# USB2MCV_REV1.net
KiCad netlist of a schematic drawn in EAGLE
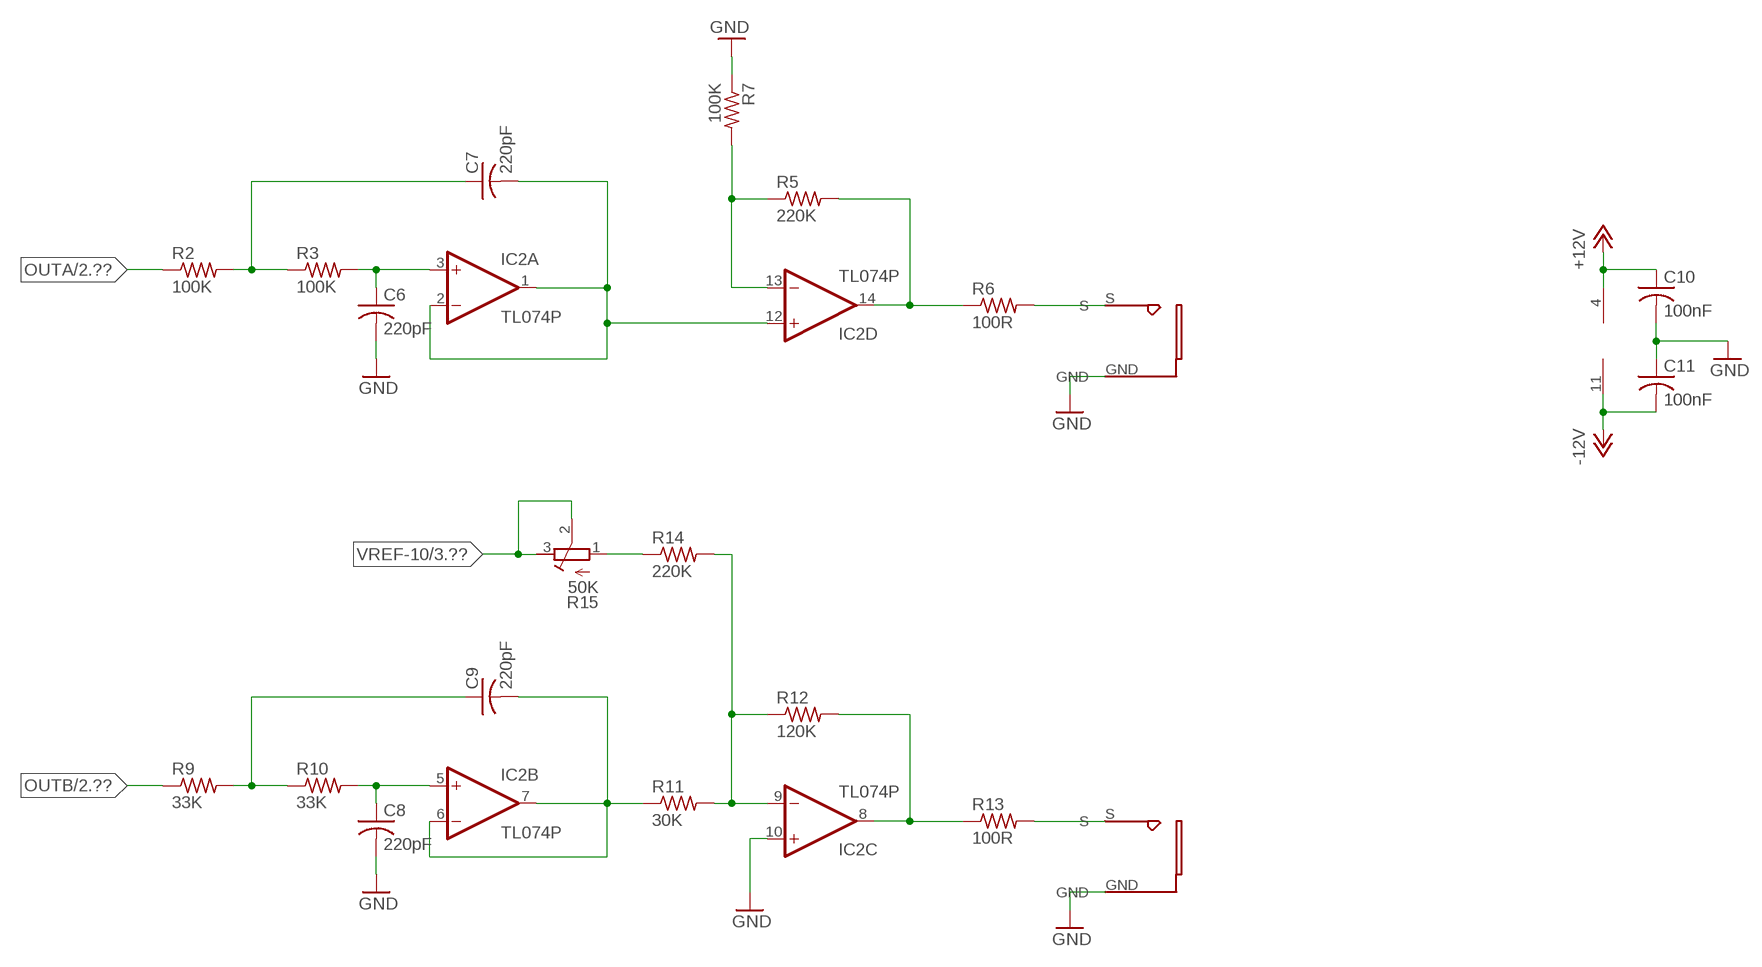
[diagram p0: schematic, sheet 1]
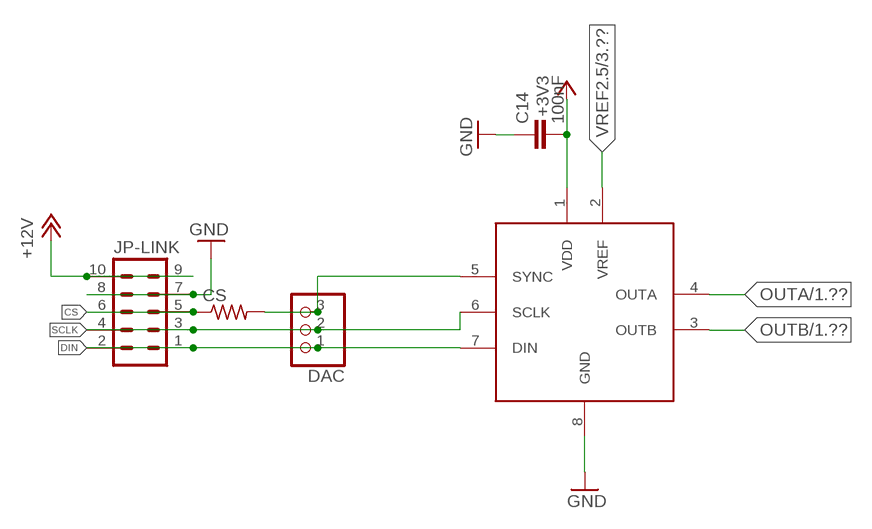
[diagram p1: schematic, sheet 2]
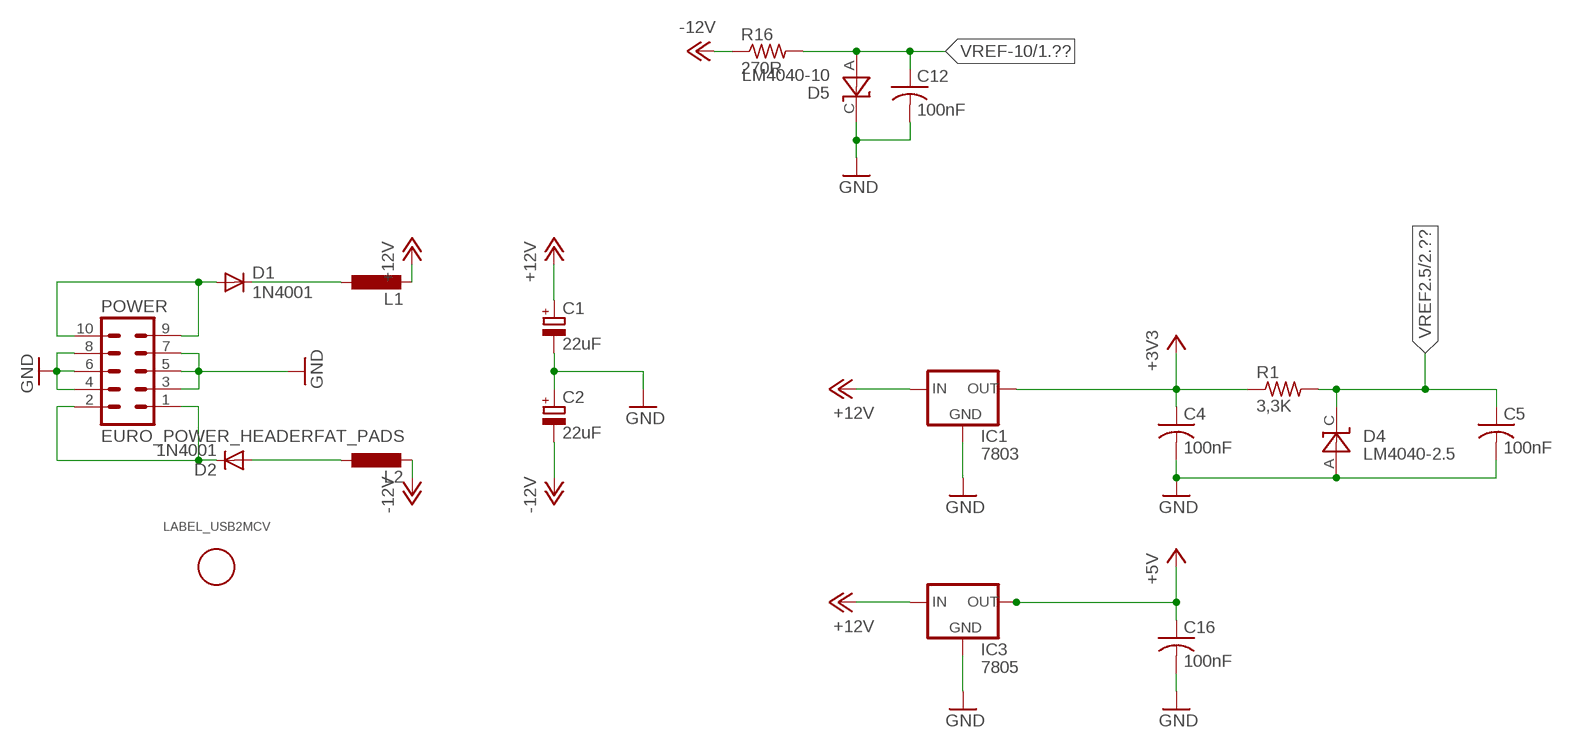
[diagram p2: schematic, sheet 3]
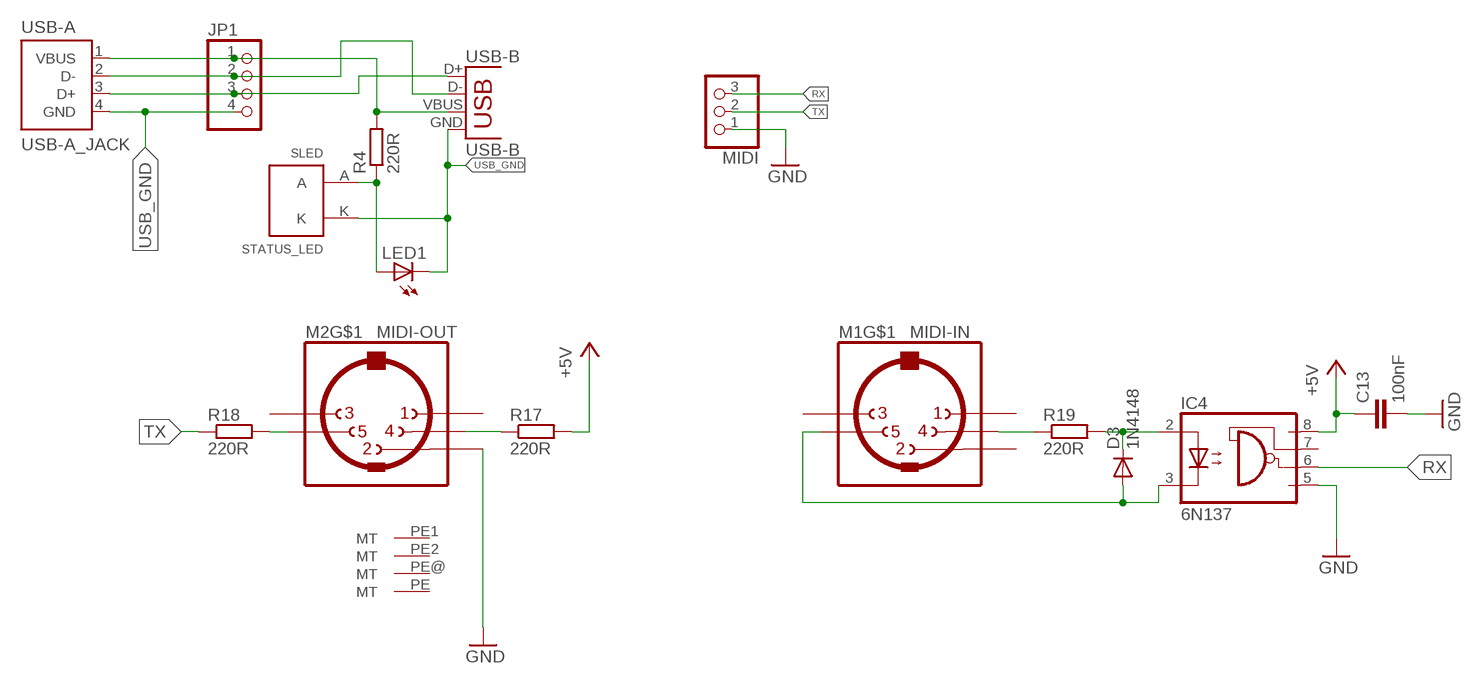
[diagram p3: schematic, sheet 4]

(export (version "E")
  (design (tool "Eeschema 10.0.6"))
  (components
    (comp (ref "C14")
      (value "100nF")
      (footprint "eagle-import:C1206K")
      (libsource (lib "eagle-import") (part "C-EUC1206K"))
    )
    (comp (ref "CS")
      (value "R-US_R0402")
      (footprint "eagle-import:R0402")
      (libsource (lib "eagle-import") (part "R-US_R0402"))
    )
    (comp (ref "DAC")
      (value "PINHD-1X3_2.54")
      (footprint "eagle-import:1X03")
      (libsource (lib "eagle-import") (part "PINHD-1X3_2.54"))
    )
    (comp (ref "IC5")
      (value "DAC8552")
      (footprint "eagle-import:MSOP-8")
      (libsource (lib "eagle-import") (part "DAC8552"))
    )
    (comp (ref "JP-LINK")
      (value "ML10")
      (footprint "eagle-import:ML10")
      (libsource (lib "eagle-import") (part "ML10"))
    )
    (comp (ref "C6")
      (value "220pF")
      (footprint "eagle-import:C1206K")
      (libsource (lib "eagle-import") (part "C-USC1206K"))
    )
    (comp (ref "C7")
      (value "220pF")
      (footprint "eagle-import:C1206K")
      (libsource (lib "eagle-import") (part "C-USC1206K"))
    )
    (comp (ref "C8")
      (value "220pF")
      (footprint "eagle-import:C1206K")
      (libsource (lib "eagle-import") (part "C-USC1206K"))
    )
    (comp (ref "C9")
      (value "220pF")
      (footprint "eagle-import:C1206K")
      (libsource (lib "eagle-import") (part "C-USC1206K"))
    )
    (comp (ref "C10")
      (value "100nF")
      (footprint "eagle-import:C1206K")
      (libsource (lib "eagle-import") (part "C-USC1206K"))
    )
    (comp (ref "C11")
      (value "100nF")
      (footprint "eagle-import:C1206K")
      (libsource (lib "eagle-import") (part "C-USC1206K"))
    )
    (comp (ref "IC2")
      (value "TL074P")
      (footprint "eagle-import:DIL14")
      (libsource (lib "eagle-import") (part "TL074P"))
    )
    (comp (ref "OUT1")
      (value "PJ302M")
      (footprint "eagle-import:PJ302M")
      (libsource (lib "eagle-import") (part "PJ302M"))
    )
    (comp (ref "OUT2")
      (value "PJ302M")
      (footprint "eagle-import:PJ302M")
      (libsource (lib "eagle-import") (part "PJ302M"))
    )
    (comp (ref "R2")
      (value "100K")
      (footprint "eagle-import:R1206")
      (libsource (lib "eagle-import") (part "R-US_R1206"))
    )
    (comp (ref "R3")
      (value "100K")
      (footprint "eagle-import:R1206")
      (libsource (lib "eagle-import") (part "R-US_R1206"))
    )
    (comp (ref "R5")
      (value "220K")
      (footprint "eagle-import:R1206")
      (libsource (lib "eagle-import") (part "R-US_R1206"))
    )
    (comp (ref "R6")
      (value "100R")
      (footprint "eagle-import:R1206")
      (libsource (lib "eagle-import") (part "R-US_R1206"))
    )
    (comp (ref "R7")
      (value "100K")
      (footprint "eagle-import:R1206")
      (libsource (lib "eagle-import") (part "R-US_R1206"))
    )
    (comp (ref "R9")
      (value "33K")
      (footprint "eagle-import:R1206")
      (libsource (lib "eagle-import") (part "R-US_R1206"))
    )
    (comp (ref "R10")
      (value "33K")
      (footprint "eagle-import:R1206")
      (libsource (lib "eagle-import") (part "R-US_R1206"))
    )
    (comp (ref "R11")
      (value "30K")
      (footprint "eagle-import:R1206")
      (libsource (lib "eagle-import") (part "R-US_R1206"))
    )
    (comp (ref "R12")
      (value "120K")
      (footprint "eagle-import:R1206")
      (libsource (lib "eagle-import") (part "R-US_R1206"))
    )
    (comp (ref "R13")
      (value "100R")
      (footprint "eagle-import:R1206")
      (libsource (lib "eagle-import") (part "R-US_R1206"))
    )
    (comp (ref "R14")
      (value "220K")
      (footprint "eagle-import:R1206")
      (libsource (lib "eagle-import") (part "R-US_R1206"))
    )
    (comp (ref "R15")
      (value "50K")
      (footprint "eagle-import:RTRIM64Y")
      (libsource (lib "eagle-import") (part "R-TRIMM64Y"))
    )
    (comp (ref "C1")
      (value "22uF")
      (footprint "eagle-import:E2-5")
      (libsource (lib "eagle-import") (part "CPOL-EUE2-5"))
    )
    (comp (ref "C2")
      (value "22uF")
      (footprint "eagle-import:E2-5")
      (libsource (lib "eagle-import") (part "CPOL-EUE2-5"))
    )
    (comp (ref "C4")
      (value "100nF")
      (footprint "eagle-import:C1206K")
      (libsource (lib "eagle-import") (part "C-USC1206K"))
    )
    (comp (ref "C5")
      (value "100nF")
      (footprint "eagle-import:C1206K")
      (libsource (lib "eagle-import") (part "C-USC1206K"))
    )
    (comp (ref "C12")
      (value "100nF")
      (footprint "eagle-import:C1206K")
      (libsource (lib "eagle-import") (part "C-USC1206K"))
    )
    (comp (ref "C16")
      (value "100nF")
      (footprint "eagle-import:C1206K")
      (libsource (lib "eagle-import") (part "C-USC1206K"))
    )
    (comp (ref "D1")
      (value "1N4001")
      (footprint "eagle-import:DO41-10")
      (libsource (lib "eagle-import") (part "1N4004"))
    )
    (comp (ref "D2")
      (value "1N4001")
      (footprint "eagle-import:DO41-10")
      (libsource (lib "eagle-import") (part "1N4004"))
    )
    (comp (ref "D4")
      (value "LM4040-2.5")
      (footprint "eagle-import:TO-92")
      (libsource (lib "eagle-import") (part "LM4040DIP"))
    )
    (comp (ref "D5")
      (value "LM4040-10")
      (footprint "eagle-import:TO-92")
      (libsource (lib "eagle-import") (part "LM4040DIP"))
    )
    (comp (ref "IC1")
      (value "7803")
      (footprint "eagle-import:78LXX")
      (libsource (lib "eagle-import") (part "78LXX"))
    )
    (comp (ref "IC3")
      (value "7805")
      (footprint "eagle-import:78LXX")
      (libsource (lib "eagle-import") (part "78LXX"))
    )
    (comp (ref "L1")
      (value "L-EU0207/10")
      (footprint "eagle-import:0207_10")
      (libsource (lib "eagle-import") (part "L-EU0207/10"))
    )
    (comp (ref "L2")
      (value "L-EU0207/10")
      (footprint "eagle-import:0207_10")
      (libsource (lib "eagle-import") (part "L-EU0207/10"))
    )
    (comp (ref "POWER")
      (value "EURO_POWER_HEADERFAT_PADS")
      (footprint "eagle-import:EURO_PWR_HEADER_FAT")
      (libsource (lib "eagle-import") (part "EURO_POWER_HEADERFAT_PADS"))
    )
    (comp (ref "R1")
      (value "3,3K")
      (footprint "eagle-import:R1206")
      (libsource (lib "eagle-import") (part "R-US_R1206"))
    )
    (comp (ref "R16")
      (value "270R")
      (footprint "eagle-import:R1206")
      (libsource (lib "eagle-import") (part "R-US_R1206"))
    )
    (comp (ref "U$1")
      (value "LABEL_USB2MCV")
      (footprint "eagle-import:LABEL_USB2DAC")
      (libsource (lib "eagle-import") (part "LABEL_USB2MCV"))
    )
    (comp (ref "C13")
      (value "100nF")
      (footprint "eagle-import:C1206K")
      (libsource (lib "eagle-import") (part "C-EUC1206K"))
    )
    (comp (ref "D3")
      (value "1N4148")
      (footprint "eagle-import:DO35-7")
      (libsource (lib "eagle-import") (part "1N4148DO35-7"))
    )
    (comp (ref "IC4")
      (value "6N137")
      (footprint "eagle-import:DIL08")
      (libsource (lib "eagle-import") (part "6N137"))
    )
    (comp (ref "JP1")
      (value "PINHD-1X4_2.54")
      (footprint "eagle-import:1X04")
      (libsource (lib "eagle-import") (part "PINHD-1X4_2.54"))
    )
    (comp (ref "LED1")
      (value "LED1206")
      (footprint "eagle-import:LED-1206")
      (libsource (lib "eagle-import") (part "LED1206"))
    )
    (comp (ref "M1")
      (value "MIDI-IN")
      (footprint "eagle-import:CP-2350")
      (libsource (lib "eagle-import") (part "MIDIJACK"))
    )
    (comp (ref "M2")
      (value "MIDI-OUT")
      (footprint "eagle-import:CP-2350")
      (libsource (lib "eagle-import") (part "MIDIJACK"))
    )
    (comp (ref "MIDI")
      (value "PINHD-1X3_2.54")
      (footprint "eagle-import:1X03")
      (libsource (lib "eagle-import") (part "PINHD-1X3_2.54"))
    )
    (comp (ref "R4")
      (value "220R")
      (footprint "eagle-import:R1206@1")
      (libsource (lib "eagle-import") (part "R-EU_R1206"))
    )
    (comp (ref "R17")
      (value "220R")
      (footprint "eagle-import:R1206@1")
      (libsource (lib "eagle-import") (part "R-EU_R1206"))
    )
    (comp (ref "R18")
      (value "220R")
      (footprint "eagle-import:R1206@1")
      (libsource (lib "eagle-import") (part "R-EU_R1206"))
    )
    (comp (ref "R19")
      (value "220R")
      (footprint "eagle-import:R1206@1")
      (libsource (lib "eagle-import") (part "R-EU_R1206"))
    )
    (comp (ref "SLED")
      (value "STATUS_LED")
      (footprint "eagle-import:STAUS-LED(DIP)")
      (libsource (lib "eagle-import") (part "STATUS_LED"))
    )
    (comp (ref "USB-A")
      (value "USB-A_JACK")
      (footprint "eagle-import:USB-A")
      (libsource (lib "eagle-import") (part "USB-A_JACK"))
    )
    (comp (ref "USB-B")
      (value "USB-B")
      (footprint "eagle-import:USB-B-PTH")
      (libsource (lib "eagle-import") (part "USBPTH"))
    )
  )
  (nets
    (net (code "1") (name "+3V3") (class "Default")
      (node (ref "C14") (pin "2") (pinfunction "2_2") (pintype "passive"))
      (node (ref "C4") (pin "1") (pinfunction "1_1") (pintype "passive"))
      (node (ref "IC1") (pin "OUT") (pinfunction "OUT_OUT") (pintype "passive"))
      (node (ref "IC5") (pin "1") (pinfunction "VDD_1") (pintype "bidirectional"))
      (node (ref "R1") (pin "1") (pinfunction "1_1") (pintype "passive"))
    )
    (net (code "2") (name "+5V") (class "Default")
      (node (ref "C13") (pin "1") (pinfunction "1_1") (pintype "passive"))
      (node (ref "C16") (pin "1") (pinfunction "1_1") (pintype "passive"))
      (node (ref "IC3") (pin "OUT") (pinfunction "OUT_OUT") (pintype "passive"))
      (node (ref "IC4") (pin "8") (pinfunction "VCC_8") (pintype "passive"))
      (node (ref "R17") (pin "2") (pinfunction "2_2") (pintype "passive"))
    )
    (net (code "3") (name "+12V") (class "Default")
      (node (ref "C1") (pin "+") (pinfunction "+_+") (pintype "passive"))
      (node (ref "C10") (pin "1") (pinfunction "1_1") (pintype "passive"))
      (node (ref "IC1") (pin "IN") (pinfunction "IN_IN") (pintype "input"))
      (node (ref "IC2") (pin "4") (pinfunction "V+_4") (pintype "power_in"))
      (node (ref "IC3") (pin "IN") (pinfunction "IN_IN") (pintype "input"))
      (node (ref "JP-LINK") (pin "10") (pinfunction "10_10") (pintype "passive"))
      (node (ref "JP-LINK") (pin "9") (pinfunction "9_9") (pintype "passive"))
      (node (ref "L1") (pin "2") (pinfunction "2_2") (pintype "passive"))
    )
    (net (code "4") (name "-12V") (class "Default")
      (node (ref "C11") (pin "2") (pinfunction "2_2") (pintype "passive"))
      (node (ref "C2") (pin "-") (pinfunction "-_-") (pintype "passive"))
      (node (ref "IC2") (pin "11") (pinfunction "V-_11") (pintype "power_in"))
      (node (ref "L2") (pin "2") (pinfunction "2_2") (pintype "passive"))
      (node (ref "R16") (pin "1") (pinfunction "1_1") (pintype "passive"))
    )
    (net (code "5") (name "CS") (class "Default")
      (node (ref "CS") (pin "1") (pinfunction "1_1") (pintype "passive"))
      (node (ref "JP-LINK") (pin "5") (pinfunction "5_5") (pintype "passive"))
      (node (ref "JP-LINK") (pin "6") (pinfunction "6_6") (pintype "passive"))
    )
    (net (code "6") (name "DIN") (class "Default")
      (node (ref "DAC") (pin "1") (pinfunction "1_1") (pintype "passive"))
      (node (ref "IC5") (pin "7") (pinfunction "DIN_7") (pintype "bidirectional"))
      (node (ref "JP-LINK") (pin "1") (pinfunction "1_1") (pintype "passive"))
      (node (ref "JP-LINK") (pin "2") (pinfunction "2_2") (pintype "passive"))
    )
    (net (code "7") (name "GND") (class "Default")
      (node (ref "C1") (pin "-") (pinfunction "-_-") (pintype "passive"))
      (node (ref "C10") (pin "2") (pinfunction "2_2") (pintype "passive"))
      (node (ref "C11") (pin "1") (pinfunction "1_1") (pintype "passive"))
      (node (ref "C12") (pin "2") (pinfunction "2_2") (pintype "passive"))
      (node (ref "C13") (pin "2") (pinfunction "2_2") (pintype "passive"))
      (node (ref "C14") (pin "1") (pinfunction "1_1") (pintype "passive"))
      (node (ref "C16") (pin "2") (pinfunction "2_2") (pintype "passive"))
      (node (ref "C2") (pin "+") (pinfunction "+_+") (pintype "passive"))
      (node (ref "C4") (pin "2") (pinfunction "2_2") (pintype "passive"))
      (node (ref "C5") (pin "2") (pinfunction "2_2") (pintype "passive"))
      (node (ref "C6") (pin "2") (pinfunction "2_2") (pintype "passive"))
      (node (ref "C8") (pin "2") (pinfunction "2_2") (pintype "passive"))
      (node (ref "D4") (pin "A") (pinfunction "A_A") (pintype "output"))
      (node (ref "D5") (pin "C") (pinfunction "C_C") (pintype "input"))
      (node (ref "IC1") (pin "GND") (pinfunction "GND_GND") (pintype "input"))
      (node (ref "IC2") (pin "10") (pinfunction "+IN_10") (pintype "input"))
      (node (ref "IC3") (pin "GND") (pinfunction "GND_GND") (pintype "input"))
      (node (ref "IC4") (pin "5") (pinfunction "GND_5") (pintype "passive"))
      (node (ref "IC5") (pin "8") (pinfunction "GND_8") (pintype "bidirectional"))
      (node (ref "JP-LINK") (pin "7") (pinfunction "7_7") (pintype "passive"))
      (node (ref "JP-LINK") (pin "8") (pinfunction "8_8") (pintype "passive"))
      (node (ref "M2") (pin "2") (pinfunction "2_2") (pintype "passive"))
      (node (ref "MIDI") (pin "1") (pinfunction "1_1") (pintype "passive"))
      (node (ref "OUT1") (pin "GND") (pinfunction "GND_GND") (pintype "bidirectional"))
      (node (ref "OUT2") (pin "GND") (pinfunction "GND_GND") (pintype "bidirectional"))
      (node (ref "POWER") (pin "3") (pinfunction "3_3") (pintype "passive"))
      (node (ref "POWER") (pin "4") (pinfunction "4_4") (pintype "passive"))
      (node (ref "POWER") (pin "5") (pinfunction "5_5") (pintype "passive"))
      (node (ref "POWER") (pin "6") (pinfunction "6_6") (pintype "passive"))
      (node (ref "POWER") (pin "7") (pinfunction "7_7") (pintype "passive"))
      (node (ref "POWER") (pin "8") (pinfunction "8_8") (pintype "passive"))
      (node (ref "R7") (pin "1") (pinfunction "1_1") (pintype "passive"))
    )
    (net (code "8") (name "Net-(C7-Pad1)") (class "Default")
      (node (ref "C7") (pin "1") (pinfunction "1_1") (pintype "passive"))
      (node (ref "R2") (pin "2") (pinfunction "2_2") (pintype "passive"))
      (node (ref "R3") (pin "1") (pinfunction "1_1") (pintype "passive"))
    )
    (net (code "9") (name "Net-(C9-Pad1)") (class "Default")
      (node (ref "C9") (pin "1") (pinfunction "1_1") (pintype "passive"))
      (node (ref "R10") (pin "1") (pinfunction "1_1") (pintype "passive"))
      (node (ref "R9") (pin "2") (pinfunction "2_2") (pintype "passive"))
    )
    (net (code "10") (name "Net-(D1-PadA)") (class "Default")
      (node (ref "D1") (pin "A") (pinfunction "A_A") (pintype "passive"))
      (node (ref "POWER") (pin "10") (pinfunction "10_10") (pintype "passive"))
      (node (ref "POWER") (pin "9") (pinfunction "9_9") (pintype "passive"))
    )
    (net (code "11") (name "Net-(D1-PadC)") (class "Default")
      (node (ref "D1") (pin "C") (pinfunction "C_C") (pintype "passive"))
      (node (ref "L1") (pin "1") (pinfunction "1_1") (pintype "passive"))
    )
    (net (code "12") (name "Net-(D2-PadA)") (class "Default")
      (node (ref "D2") (pin "A") (pinfunction "A_A") (pintype "passive"))
      (node (ref "L2") (pin "1") (pinfunction "1_1") (pintype "passive"))
    )
    (net (code "13") (name "Net-(D2-PadC)") (class "Default")
      (node (ref "D2") (pin "C") (pinfunction "C_C") (pintype "passive"))
      (node (ref "POWER") (pin "1") (pinfunction "1_1") (pintype "passive"))
      (node (ref "POWER") (pin "2") (pinfunction "2_2") (pintype "passive"))
    )
    (net (code "14") (name "Net-(IC2A-+IN)") (class "Default")
      (node (ref "C6") (pin "1") (pinfunction "1_1") (pintype "passive"))
      (node (ref "IC2") (pin "3") (pinfunction "+IN_3") (pintype "input"))
      (node (ref "R3") (pin "2") (pinfunction "2_2") (pintype "passive"))
    )
    (net (code "15") (name "Net-(IC2A--IN)") (class "Default")
      (node (ref "C7") (pin "2") (pinfunction "2_2") (pintype "passive"))
      (node (ref "IC2") (pin "1") (pinfunction "OUT_1") (pintype "output"))
      (node (ref "IC2") (pin "12") (pinfunction "+IN_12") (pintype "input"))
      (node (ref "IC2") (pin "2") (pinfunction "-IN_2") (pintype "input"))
    )
    (net (code "16") (name "Net-(IC2B-+IN)") (class "Default")
      (node (ref "C8") (pin "1") (pinfunction "1_1") (pintype "passive"))
      (node (ref "IC2") (pin "5") (pinfunction "+IN_5") (pintype "input"))
      (node (ref "R10") (pin "2") (pinfunction "2_2") (pintype "passive"))
    )
    (net (code "17") (name "Net-(IC2B--IN)") (class "Default")
      (node (ref "C9") (pin "2") (pinfunction "2_2") (pintype "passive"))
      (node (ref "IC2") (pin "6") (pinfunction "-IN_6") (pintype "input"))
      (node (ref "IC2") (pin "7") (pinfunction "OUT_7") (pintype "output"))
      (node (ref "R11") (pin "1") (pinfunction "1_1") (pintype "passive"))
    )
    (net (code "18") (name "Net-(IC2C--IN)") (class "Default")
      (node (ref "IC2") (pin "9") (pinfunction "-IN_9") (pintype "input"))
      (node (ref "R11") (pin "2") (pinfunction "2_2") (pintype "passive"))
      (node (ref "R12") (pin "1") (pinfunction "1_1") (pintype "passive"))
      (node (ref "R14") (pin "2") (pinfunction "2_2") (pintype "passive"))
    )
    (net (code "19") (name "Net-(IC2C-OUT)") (class "Default")
      (node (ref "IC2") (pin "8") (pinfunction "OUT_8") (pintype "output"))
      (node (ref "R12") (pin "2") (pinfunction "2_2") (pintype "passive"))
      (node (ref "R13") (pin "1") (pinfunction "1_1") (pintype "passive"))
    )
    (net (code "20") (name "Net-(IC2D--IN)") (class "Default")
      (node (ref "IC2") (pin "13") (pinfunction "-IN_13") (pintype "input"))
      (node (ref "R5") (pin "1") (pinfunction "1_1") (pintype "passive"))
      (node (ref "R7") (pin "2") (pinfunction "2_2") (pintype "passive"))
    )
    (net (code "21") (name "Net-(IC2D-OUT)") (class "Default")
      (node (ref "IC2") (pin "14") (pinfunction "OUT_14") (pintype "output"))
      (node (ref "R5") (pin "2") (pinfunction "2_2") (pintype "passive"))
      (node (ref "R6") (pin "1") (pinfunction "1_1") (pintype "passive"))
    )
    (net (code "22") (name "Net-(IC4-A)") (class "Default")
      (node (ref "D3") (pin "C") (pinfunction "C_C") (pintype "passive"))
      (node (ref "IC4") (pin "2") (pinfunction "A_2") (pintype "passive"))
      (node (ref "R19") (pin "2") (pinfunction "2_2") (pintype "passive"))
    )
    (net (code "23") (name "Net-(IC4-C)") (class "Default")
      (node (ref "D3") (pin "A") (pinfunction "A_A") (pintype "passive"))
      (node (ref "IC4") (pin "3") (pinfunction "C_3") (pintype "passive"))
      (node (ref "M1") (pin "5") (pinfunction "5_5") (pintype "passive"))
    )
    (net (code "24") (name "Net-(IC5-SYNC)") (class "Default")
      (node (ref "CS") (pin "2") (pinfunction "2_2") (pintype "passive"))
      (node (ref "DAC") (pin "3") (pinfunction "3_3") (pintype "passive"))
      (node (ref "IC5") (pin "5") (pinfunction "SYNC_5") (pintype "bidirectional"))
    )
    (net (code "25") (name "Net-(LED1-PadA)") (class "Default")
      (node (ref "LED1") (pin "A") (pinfunction "A_A") (pintype "passive"))
      (node (ref "R4") (pin "1") (pinfunction "1_1") (pintype "passive"))
      (node (ref "SLED") (pin "A") (pinfunction "A_A") (pintype "bidirectional"))
    )
    (net (code "26") (name "Net-(M1-Pad4)") (class "Default")
      (node (ref "M1") (pin "4") (pinfunction "4_4") (pintype "passive"))
      (node (ref "R19") (pin "1") (pinfunction "1_1") (pintype "passive"))
    )
    (net (code "27") (name "Net-(M2-Pad4)") (class "Default")
      (node (ref "M2") (pin "4") (pinfunction "4_4") (pintype "passive"))
      (node (ref "R17") (pin "1") (pinfunction "1_1") (pintype "passive"))
    )
    (net (code "28") (name "Net-(M2-Pad5)") (class "Default")
      (node (ref "M2") (pin "5") (pinfunction "5_5") (pintype "passive"))
      (node (ref "R18") (pin "2") (pinfunction "2_2") (pintype "passive"))
    )
    (net (code "29") (name "Net-(OUT1-PadS)") (class "Default")
      (node (ref "OUT1") (pin "S") (pinfunction "S_S") (pintype "bidirectional"))
      (node (ref "R6") (pin "2") (pinfunction "2_2") (pintype "passive"))
    )
    (net (code "30") (name "Net-(OUT2-PadS)") (class "Default")
      (node (ref "OUT2") (pin "S") (pinfunction "S_S") (pintype "bidirectional"))
      (node (ref "R13") (pin "2") (pinfunction "2_2") (pintype "passive"))
    )
    (net (code "31") (name "Net-(R15-E)") (class "Default")
      (node (ref "R14") (pin "1") (pinfunction "1_1") (pintype "passive"))
      (node (ref "R15") (pin "1") (pinfunction "E_1") (pintype "passive"))
    )
    (net (code "32") (name "Net-(USB-A-D+)") (class "Default")
      (node (ref "JP1") (pin "3") (pinfunction "3_3") (pintype "passive"))
      (node (ref "USB-A") (pin "3") (pinfunction "D+_3") (pintype "bidirectional"))
      (node (ref "USB-B") (pin "D+") (pinfunction "D+_D+") (pintype "bidirectional"))
    )
    (net (code "33") (name "Net-(USB-A-D-)") (class "Default")
      (node (ref "JP1") (pin "2") (pinfunction "2_2") (pintype "passive"))
      (node (ref "USB-A") (pin "2") (pinfunction "D-_2") (pintype "bidirectional"))
      (node (ref "USB-B") (pin "D-") (pinfunction "D-_D-") (pintype "bidirectional"))
    )
    (net (code "34") (name "Net-(USB-A-VBUS)") (class "Default")
      (node (ref "JP1") (pin "1") (pinfunction "1_1") (pintype "passive"))
      (node (ref "R4") (pin "2") (pinfunction "2_2") (pintype "passive"))
      (node (ref "USB-A") (pin "1") (pinfunction "VBUS_1") (pintype "bidirectional"))
      (node (ref "USB-B") (pin "VBUS") (pinfunction "VBUS_VBUS") (pintype "bidirectional"))
    )
    (net (code "35") (name "OUTA") (class "Default")
      (node (ref "IC5") (pin "4") (pinfunction "OUTA_4") (pintype "bidirectional"))
      (node (ref "R2") (pin "1") (pinfunction "1_1") (pintype "passive"))
    )
    (net (code "36") (name "OUTB") (class "Default")
      (node (ref "IC5") (pin "3") (pinfunction "OUTB_3") (pintype "bidirectional"))
      (node (ref "R9") (pin "1") (pinfunction "1_1") (pintype "passive"))
    )
    (net (code "37") (name "RX") (class "Default")
      (node (ref "IC4") (pin "6") (pinfunction "VO_6") (pintype "passive"))
      (node (ref "MIDI") (pin "3") (pinfunction "3_3") (pintype "passive"))
    )
    (net (code "38") (name "SCLK") (class "Default")
      (node (ref "DAC") (pin "2") (pinfunction "2_2") (pintype "passive"))
      (node (ref "IC5") (pin "6") (pinfunction "SCLK_6") (pintype "bidirectional"))
      (node (ref "JP-LINK") (pin "3") (pinfunction "3_3") (pintype "passive"))
      (node (ref "JP-LINK") (pin "4") (pinfunction "4_4") (pintype "passive"))
    )
    (net (code "39") (name "TX") (class "Default")
      (node (ref "MIDI") (pin "2") (pinfunction "2_2") (pintype "passive"))
      (node (ref "R18") (pin "1") (pinfunction "1_1") (pintype "passive"))
    )
    (net (code "40") (name "USB_GND") (class "Default")
      (node (ref "JP1") (pin "4") (pinfunction "4_4") (pintype "passive"))
      (node (ref "LED1") (pin "C") (pinfunction "C_C") (pintype "passive"))
      (node (ref "SLED") (pin "K") (pinfunction "K_K") (pintype "bidirectional"))
      (node (ref "USB-A") (pin "4") (pinfunction "GND_4") (pintype "bidirectional"))
      (node (ref "USB-B") (pin "GND") (pinfunction "GND_GND") (pintype "bidirectional"))
    )
    (net (code "41") (name "VREF-10") (class "Default")
      (node (ref "C12") (pin "1") (pinfunction "1_1") (pintype "passive"))
      (node (ref "D5") (pin "A") (pinfunction "A_A") (pintype "output"))
      (node (ref "R15") (pin "2") (pinfunction "S_2") (pintype "passive"))
      (node (ref "R15") (pin "3") (pinfunction "A_3") (pintype "passive"))
      (node (ref "R16") (pin "2") (pinfunction "2_2") (pintype "passive"))
    )
    (net (code "42") (name "VREF2.5") (class "Default")
      (node (ref "C5") (pin "1") (pinfunction "1_1") (pintype "passive"))
      (node (ref "D4") (pin "C") (pinfunction "C_C") (pintype "input"))
      (node (ref "IC5") (pin "2") (pinfunction "VREF_2") (pintype "bidirectional"))
      (node (ref "R1") (pin "2") (pinfunction "2_2") (pintype "passive"))
    )
    (net (code "43") (name "unconnected-(IC4-VE-Pad7)") (class "Default")
      (node (ref "IC4") (pin "7") (pinfunction "VE_7") (pintype "passive"))
    )
    (net (code "44") (name "unconnected-(M1-Pad1)") (class "Default")
      (node (ref "M1") (pin "1") (pinfunction "1_1") (pintype "passive"))
    )
    (net (code "45") (name "unconnected-(M1-Pad2)") (class "Default")
      (node (ref "M1") (pin "2") (pinfunction "2_2") (pintype "passive"))
    )
    (net (code "46") (name "unconnected-(M1-Pad3)") (class "Default")
      (node (ref "M1") (pin "3") (pinfunction "3_3") (pintype "passive"))
    )
    (net (code "47") (name "unconnected-(M2-Pad1)") (class "Default")
      (node (ref "M2") (pin "1") (pinfunction "1_1") (pintype "passive"))
    )
    (net (code "48") (name "unconnected-(M2-Pad3)") (class "Default")
      (node (ref "M2") (pin "3") (pinfunction "3_3") (pintype "passive"))
    )
    (net (code "49") (name "unconnected-(M2B-MT-PadPE)") (class "Default")
      (node (ref "M2") (pin "PE") (pinfunction "MT_PE") (pintype "passive"))
    )
    (net (code "50") (name "unconnected-(M2C-MT-PadPE@)") (class "Default")
      (node (ref "M2") (pin "PE@") (pinfunction "MT_PE@") (pintype "passive"))
    )
    (net (code "51") (name "unconnected-(M2D-MT-PadPE1)") (class "Default")
      (node (ref "M2") (pin "PE1") (pinfunction "MT_PE1") (pintype "passive"))
    )
    (net (code "52") (name "unconnected-(M2E-MT-PadPE2)") (class "Default")
      (node (ref "M2") (pin "PE2") (pinfunction "MT_PE2") (pintype "passive"))
    )
  )
)
